# drv.net
KiCad netlist of a schematic drawn in Altium Designer
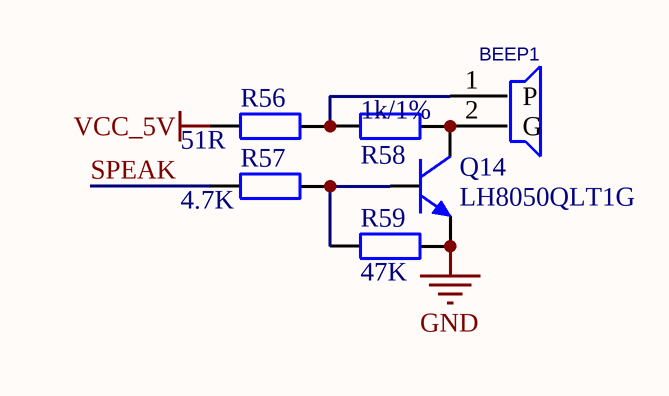
[diagram p0: drv.SchDoc]

(export (version "E")
  (design (tool "Eeschema 10.0.6"))
  (components
    (comp (ref "BEEP1")
      (value "BEEP-9.5X5.5")
      (footprint "BEEP-9.5X5.5")
      (libsource (lib "MINI-V3") (part "BEEP-9.5X5.5"))
    )
    (comp (ref "Q14")
      (value "LH8050QLT1G")
      (footprint "SOT-23")
      (description "NPN")
      (libsource (lib "XiaoyI") (part "NPN-1"))
    )
    (comp (ref "R56")
      (value "51R")
      (footprint "0603R")
      (description "贴片电阻 5%")
      (libsource (lib "") (part "RES0_1"))
    )
    (comp (ref "R57")
      (value "4.7K")
      (footprint "0603R")
      (description "贴片电阻 5%")
      (libsource (lib "ABB") (part "RES0"))
    )
    (comp (ref "R58")
      (value "1k/1%")
      (footprint "0603R")
      (description "贴片电阻 5%")
      (libsource (lib "") (part "RES0_1"))
    )
    (comp (ref "R59")
      (value "47K")
      (footprint "0603R")
      (description "贴片电阻 5%")
      (libsource (lib "ABB") (part "RES0"))
    )
  )
  (nets
    (net (code "1") (name "/SPEAK") (class "Default")
      (node (ref "R57") (pin "1") (pinfunction "1_1") (pintype "passive"))
    )
    (net (code "2") (name "GND") (class "Default")
      (node (ref "Q14") (pin "2") (pinfunction "E_2") (pintype "passive"))
      (node (ref "R59") (pin "2") (pinfunction "2_2") (pintype "passive"))
    )
    (net (code "3") (name "Net-(BEEP1-G)") (class "Default")
      (node (ref "BEEP1") (pin "2") (pinfunction "G_2") (pintype "passive"))
      (node (ref "Q14") (pin "3") (pinfunction "C_3") (pintype "passive"))
      (node (ref "R58") (pin "1") (pinfunction "1_1") (pintype "passive"))
    )
    (net (code "4") (name "Net-(BEEP1-P)") (class "Default")
      (node (ref "BEEP1") (pin "1") (pinfunction "P_1") (pintype "passive"))
      (node (ref "R56") (pin "1") (pinfunction "1_1") (pintype "passive"))
      (node (ref "R58") (pin "2") (pinfunction "2_2") (pintype "passive"))
    )
    (net (code "5") (name "Net-(Q14-B)") (class "Default")
      (node (ref "Q14") (pin "1") (pinfunction "B_1") (pintype "passive"))
      (node (ref "R57") (pin "2") (pinfunction "2_2") (pintype "passive"))
      (node (ref "R59") (pin "1") (pinfunction "1_1") (pintype "passive"))
    )
    (net (code "6") (name "VCC_5V") (class "Default")
      (node (ref "R56") (pin "2") (pinfunction "2_2") (pintype "passive"))
    )
  )
)
